# MPU6050_Schematic.net
KiCad netlist of a schematic drawn in Altium Designer
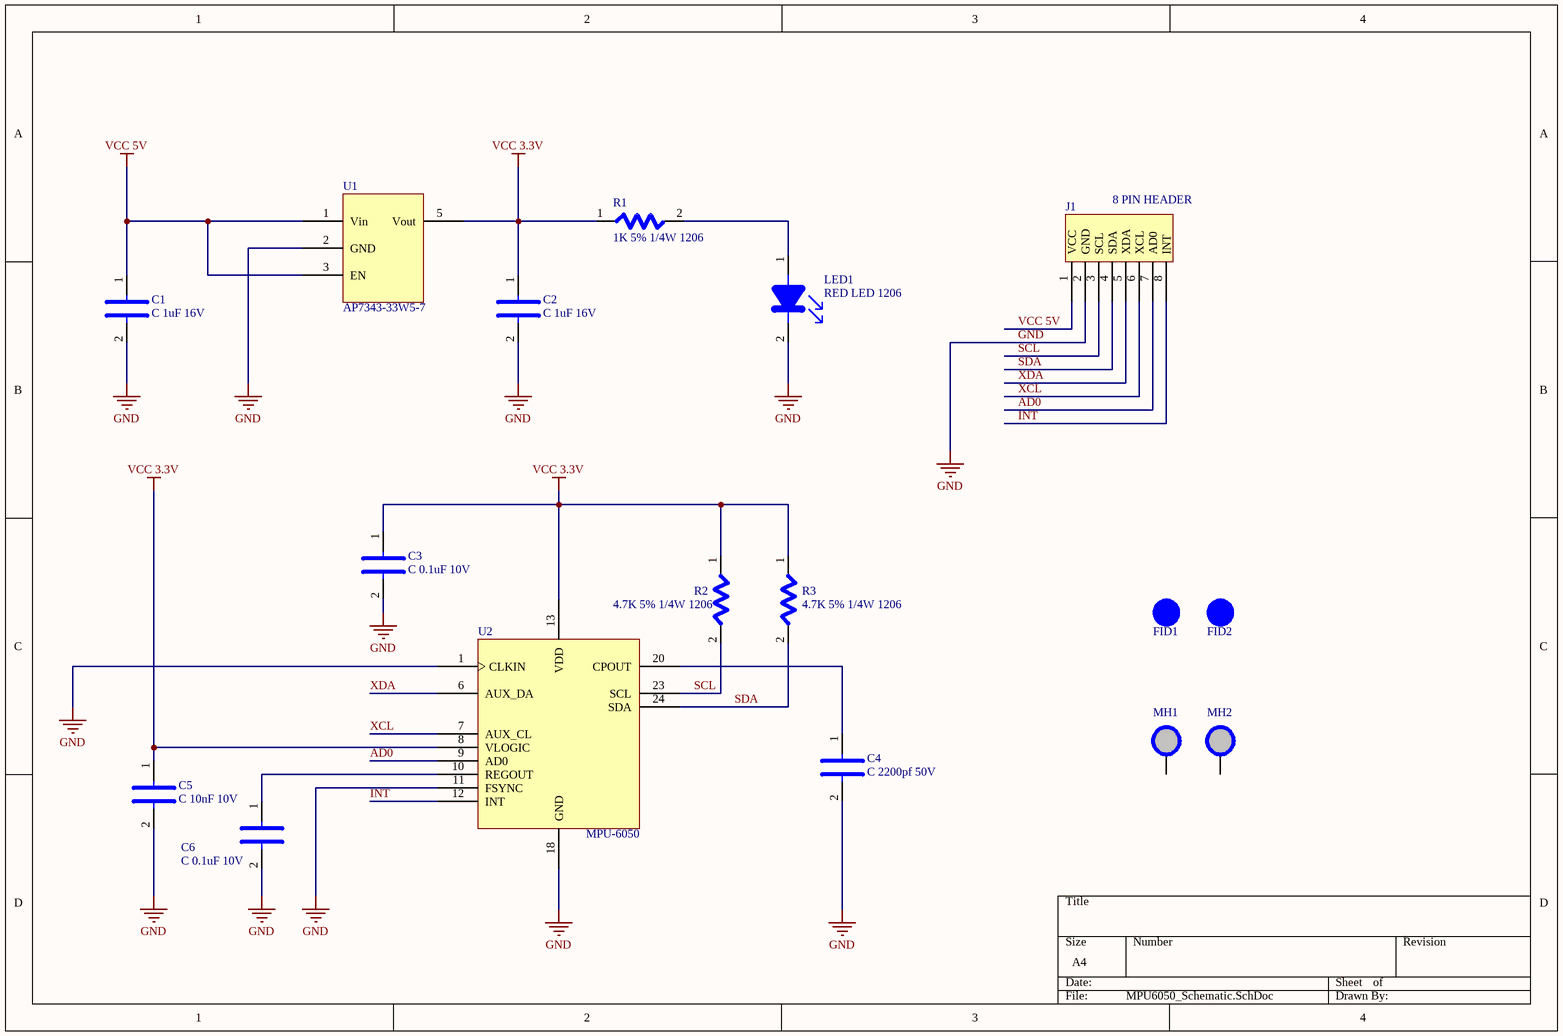
[diagram p0: MPU6050_Schematic.SchDoc]

(export (version "E")
  (design (tool "Eeschema 10.0.6"))
  (components
    (comp (ref "C1")
      (value "C 1uF 16V")
      (footprint "CAP CER 1UF 10V X7R 1206")
      (description "1 µF ±10% 10V Capacitores cerámicos X7R 1206 (3216 métrico)")
      (fields (field (name "MANUFACTURER") "KEMET"))
      (libsource (lib "MPU6050_SCHLIB") (part "CAP CER 1UF 10V X7R 1206"))
    )
    (comp (ref "C2")
      (value "C 1uF 16V")
      (footprint "CAP CER 1UF 10V X7R 1206")
      (description "1 µF ±10% 10V Capacitores cerámicos X7R 1206 (3216 métrico)")
      (fields (field (name "MANUFACTURER") "KEMET"))
      (libsource (lib "MPU6050_SCHLIB") (part "CAP CER 1UF 10V X7R 1206"))
    )
    (comp (ref "C3")
      (value "C 0.1uF 10V")
      (footprint "CAP CER 0.1UF 10V X7R 1206")
      (description "0.1 µF ±10% 10V Capacitores cerámicos X7R 1206 (3216 métrico)")
      (fields (field (name "MANUFACTURER") "KEMET"))
      (libsource (lib "MPU6050_SCHLIB") (part "CAP CER 0.1UF 10V X7R 1206"))
    )
    (comp (ref "C4")
      (value "C 2200pf 50V")
      (footprint "CAP CER 2200PF 50V NP0 1206")
      (description "CAP CER 2200PF 50V NP0 1206")
      (fields (field (name "MANUFACTURER") "KEMET"))
      (libsource (lib "MPU6050_SCHLIB") (part "CAP CER 2200PF 50V NP0 1206"))
    )
    (comp (ref "C5")
      (value "C 10nF 10V")
      (footprint "CAP CER 1206 10NF 10V ULTRA STAB")
      (description "10000 pF ±1% 10V Capacitores cerámicos X8R 1206 (3216 métrico)")
      (fields (field (name "MANUFACTURER") "KEMET"))
      (libsource (lib "MPU6050_SCHLIB") (part "CAP CER 1206 10NF 10V ULTRA STAB"))
    )
    (comp (ref "C6")
      (value "C 0.1uF 10V")
      (footprint "CAP CER 0.1UF 10V X7R 1206")
      (description "0.1 µF ±10% 10V Capacitores cerámicos X7R 1206 (3216 métrico)")
      (fields (field (name "MANUFACTURER") "KEMET"))
      (libsource (lib "MPU6050_SCHLIB") (part "CAP CER 0.1UF 10V X7R 1206"))
    )
    (comp (ref "FID1")
      (value "FID_1mm")
      (footprint "FID_40_120")
      (description "Fiducial 40mil Diameter, 120mil Mask")
      (libsource (lib "MPU6050_SCHLIB") (part "FID_1mm"))
    )
    (comp (ref "FID2")
      (value "FID_1mm")
      (footprint "FID_40_120")
      (description "Fiducial 40mil Diameter, 120mil Mask")
      (libsource (lib "MPU6050_SCHLIB") (part "FID_1mm"))
    )
    (comp (ref "J1")
      (value "8 PIN HEADER")
      (footprint "CONN HEADER VERT 8POS 3.96MM")
      (description "Cabezal de conector Orificio pasante 8 posiciones 0.156\" (3.96mm)")
      (fields (field (name "MANUFACTURER") "TE Connectivity AMP Connectors"))
      (libsource (lib "MPU6050_SCHLIB") (part "CONN HEADER VERT 8POS 3.96MM"))
    )
    (comp (ref "LED1")
      (value "RED LED 1206")
      (footprint "RES SMD 1K OHM 5% 1/4W 1206")
      (description "Rojo 630nm Indicación led: discreta 1.5V 1206 (3216 métrico)")
      (fields (field (name "MANUFACTURER") "Venkel"))
      (libsource (lib "MPU6050_SCHLIB") (part "LED 1206 FLAT LENS RED"))
    )
    (comp (ref "MH1")
      (value "MH_3.2mmD")
      (footprint "MH 7.4mmD 3.2mmDirll No plated")
      (description "MH 7..4mmD 3.2mmDrill Non plated")
      (libsource (lib "MPU6050_SCHLIB") (part "MH_3.2mmD"))
    )
    (comp (ref "MH2")
      (value "MH_3.2mmD")
      (footprint "MH 7.4mmD 3.2mmDirll No plated")
      (description "MH 7..4mmD 3.2mmDrill Non plated")
      (libsource (lib "MPU6050_SCHLIB") (part "MH_3.2mmD"))
    )
    (comp (ref "R1")
      (value "1K 5% 1/4W 1206")
      (footprint "RES SMD 1K OHM 5% 1/4W 1206")
      (description "1 kOhms ±5% 0.25W, 1/4W Resistencia en microprocesador 1206 (3216 métrico) - Película gruesa")
      (fields (field (name "MANUFACTURER") "Yageo"))
      (libsource (lib "MPU6050_SCHLIB") (part "RES SMD 1K OHM 5% 1/4W 1206"))
    )
    (comp (ref "R2")
      (value "4.7K 5% 1/4W 1206")
      (footprint "RES SMD 4.7K OHM 5% 1/4W 1206")
      (fields (field (name "MANUFACTURER") "Yageo"))
      (libsource (lib "MPU6050_SCHLIB") (part "RES 4.7K OHM 5% 1/4W 1206"))
    )
    (comp (ref "R3")
      (value "4.7K 5% 1/4W 1206")
      (footprint "RES SMD 4.7K OHM 5% 1/4W 1206")
      (fields (field (name "MANUFACTURER") "Yageo"))
      (libsource (lib "MPU6050_SCHLIB") (part "RES 4.7K OHM 5% 1/4W 1206"))
    )
    (comp (ref "U1")
      (value "AP7343-33W5-7")
      (footprint "AP7343-33W5-7")
      (description "Low dropout regulator with high output voltage. 3.3V 300mA")
      (fields (field (name "MANUFACTURER") "DIODES Incorporated"))
      (libsource (lib "MPU6050_SCHLIB") (part "AP7343-33W5-7"))
    )
    (comp (ref "U2")
      (value "MPU-6050")
      (footprint "MPU6050")
      (description "Acelerometer, gyro, 6 axis")
      (fields (field (name "MANUFACTURER") "TDK InvenSense"))
      (libsource (lib "MPU6050_SCHLIB") (part "MPU-6050"))
    )
  )
  (nets
    (net (code "1") (name "/AD0") (class "Default")
      (node (ref "J1") (pin "7") (pinfunction "AD0_7") (pintype "passive"))
      (node (ref "U2") (pin "9") (pinfunction "AD0_9") (pintype "passive"))
    )
    (net (code "2") (name "/INT") (class "Default")
      (node (ref "J1") (pin "8") (pinfunction "INT_8") (pintype "passive"))
      (node (ref "U2") (pin "12") (pinfunction "INT_12") (pintype "passive"))
    )
    (net (code "3") (name "/SCL") (class "Default")
      (node (ref "J1") (pin "3") (pinfunction "SCL_3") (pintype "passive"))
      (node (ref "R2") (pin "2") (pinfunction "2_2") (pintype "passive"))
      (node (ref "U2") (pin "23") (pinfunction "SCL_23") (pintype "passive"))
    )
    (net (code "4") (name "/SDA") (class "Default")
      (node (ref "J1") (pin "4") (pinfunction "SDA_4") (pintype "passive"))
      (node (ref "R3") (pin "2") (pinfunction "2_2") (pintype "passive"))
      (node (ref "U2") (pin "24") (pinfunction "SDA_24") (pintype "passive"))
    )
    (net (code "5") (name "/XCL") (class "Default")
      (node (ref "J1") (pin "6") (pinfunction "XCL_6") (pintype "passive"))
      (node (ref "U2") (pin "7") (pinfunction "AUX_CL_7") (pintype "passive"))
    )
    (net (code "6") (name "/XDA") (class "Default")
      (node (ref "J1") (pin "5") (pinfunction "XDA_5") (pintype "passive"))
      (node (ref "U2") (pin "6") (pinfunction "AUX_DA_6") (pintype "passive"))
    )
    (net (code "7") (name "GND") (class "Default")
      (node (ref "C1") (pin "2") (pinfunction "2_2") (pintype "passive"))
      (node (ref "C2") (pin "2") (pinfunction "2_2") (pintype "passive"))
      (node (ref "C3") (pin "2") (pinfunction "2_2") (pintype "passive"))
      (node (ref "C4") (pin "2") (pinfunction "2_2") (pintype "passive"))
      (node (ref "C5") (pin "2") (pinfunction "2_2") (pintype "passive"))
      (node (ref "C6") (pin "2") (pinfunction "2_2") (pintype "passive"))
      (node (ref "J1") (pin "2") (pinfunction "GND_2") (pintype "passive"))
      (node (ref "LED1") (pin "2") (pinfunction "2_2") (pintype "passive"))
      (node (ref "U1") (pin "2") (pinfunction "GND_2") (pintype "passive"))
      (node (ref "U2") (pin "1") (pinfunction "CLKIN_1") (pintype "passive"))
      (node (ref "U2") (pin "11") (pinfunction "FSYNC_11") (pintype "passive"))
      (node (ref "U2") (pin "18") (pinfunction "GND_18") (pintype "passive"))
    )
    (net (code "8") (name "Net-(LED1-Pad1)") (class "Default")
      (node (ref "LED1") (pin "1") (pinfunction "1_1") (pintype "passive"))
      (node (ref "R1") (pin "2") (pinfunction "2_2") (pintype "passive"))
    )
    (net (code "9") (name "Net-(U2-CPOUT)") (class "Default")
      (node (ref "C4") (pin "1") (pinfunction "1_1") (pintype "passive"))
      (node (ref "U2") (pin "20") (pinfunction "CPOUT_20") (pintype "passive"))
    )
    (net (code "10") (name "Net-(U2-REGOUT)") (class "Default")
      (node (ref "C6") (pin "1") (pinfunction "1_1") (pintype "passive"))
      (node (ref "U2") (pin "10") (pinfunction "REGOUT_10") (pintype "passive"))
    )
    (net (code "11") (name "VCC 3.3V") (class "Default")
      (node (ref "C2") (pin "1") (pinfunction "1_1") (pintype "passive"))
      (node (ref "C3") (pin "1") (pinfunction "1_1") (pintype "passive"))
      (node (ref "C5") (pin "1") (pinfunction "1_1") (pintype "passive"))
      (node (ref "R1") (pin "1") (pinfunction "1_1") (pintype "passive"))
      (node (ref "R2") (pin "1") (pinfunction "1_1") (pintype "passive"))
      (node (ref "R3") (pin "1") (pinfunction "1_1") (pintype "passive"))
      (node (ref "U1") (pin "5") (pinfunction "Vout_5") (pintype "passive"))
      (node (ref "U2") (pin "13") (pinfunction "VDD_13") (pintype "passive"))
      (node (ref "U2") (pin "8") (pinfunction "VLOGIC_8") (pintype "passive"))
    )
    (net (code "12") (name "VCC 5V") (class "Default")
      (node (ref "C1") (pin "1") (pinfunction "1_1") (pintype "passive"))
      (node (ref "J1") (pin "1") (pinfunction "VCC_1") (pintype "passive"))
      (node (ref "U1") (pin "1") (pinfunction "Vin_1") (pintype "passive"))
      (node (ref "U1") (pin "3") (pinfunction "EN_3") (pintype "passive"))
    )
    (net (code "13") (name "unconnected-(MH1-Pad1)") (class "Default")
      (node (ref "MH1") (pin "1") (pinfunction "1_1") (pintype "passive"))
    )
    (net (code "14") (name "unconnected-(MH2-Pad1)") (class "Default")
      (node (ref "MH2") (pin "1") (pinfunction "1_1") (pintype "passive"))
    )
  )
)
